# promini1via.net
KiCad netlist of a schematic drawn in EAGLE
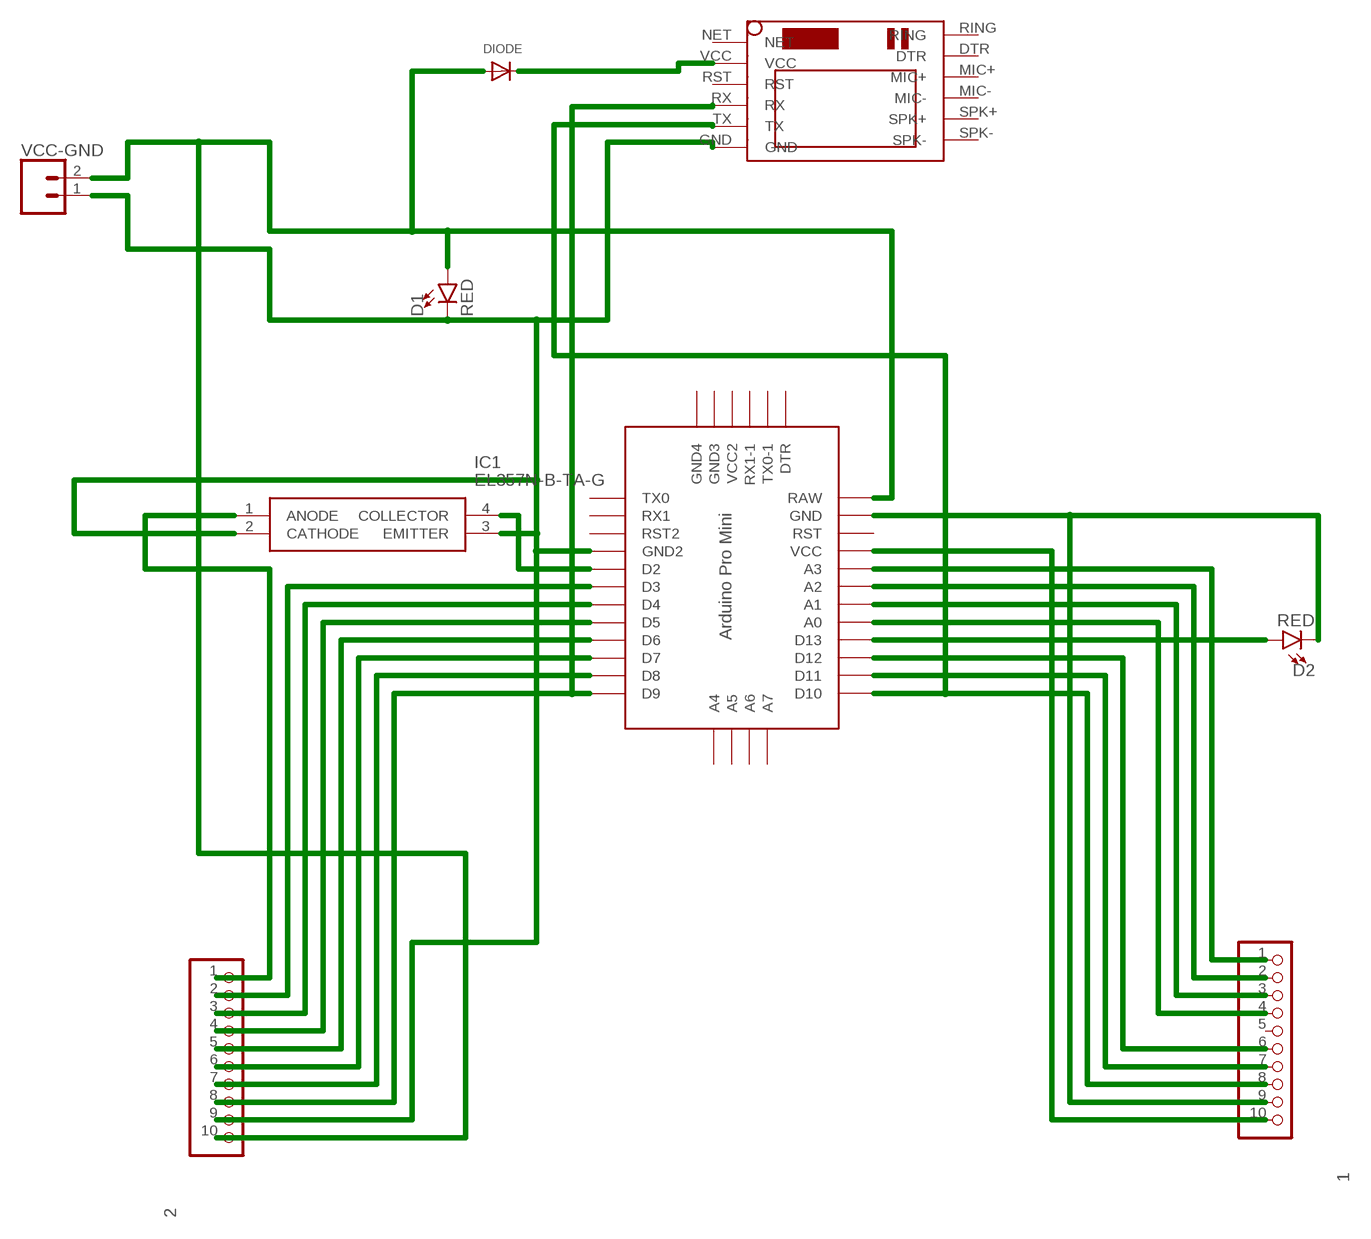
[diagram p0: schematic, sheet 1]

(export (version "E")
  (design (tool "Eeschema 10.0.6"))
  (components
    (comp (ref "1")
      (value "PINHD-1X10")
      (footprint "eagle-import:1X10")
      (libsource (lib "eagle-import") (part "PINHD-1X10"))
    )
    (comp (ref "2")
      (value "PINHD-1X10")
      (footprint "eagle-import:1X10")
      (libsource (lib "eagle-import") (part "PINHD-1X10"))
    )
    (comp (ref "D1")
      (value "RED")
      (footprint "eagle-import:LED-1206")
      (libsource (lib "eagle-import") (part "LED-RED1206"))
    )
    (comp (ref "D2")
      (value "RED")
      (footprint "eagle-import:LED-1206")
      (libsource (lib "eagle-import") (part "LED-RED1206"))
    )
    (comp (ref "DIODE")
      (value "DIODESOD-323F")
      (footprint "eagle-import:SOD-323F")
      (libsource (lib "eagle-import") (part "DIODESOD-323F"))
    )
    (comp (ref "IC1")
      (value "EL357N-B-TA-G")
      (footprint "eagle-import:SOP254P700X200-4N")
      (libsource (lib "eagle-import") (part "EL357N-B-TA-G"))
    )
    (comp (ref "PROMINI")
      (value "PRO-MINI")
      (footprint "eagle-import:PRO-MINI")
      (libsource (lib "eagle-import") (part "PRO-MINI"))
    )
    (comp (ref "U$1")
      (value "SIM800LMODULE")
      (footprint "eagle-import:SIM800LMODULE")
      (libsource (lib "eagle-import") (part "SIM800LMODULE"))
    )
    (comp (ref "VCC-GND")
      (value "CONN_023.5MM")
      (footprint "eagle-import:SCREWTERMINAL-3.5MM-2")
      (libsource (lib "eagle-import") (part "CONN_023.5MM"))
    )
  )
  (nets
    (net (code "1") (name "Net-(1-Pad1)") (class "Default")
      (node (ref "1") (pin "1") (pinfunction "1_1") (pintype "passive"))
      (node (ref "PROMINI") (pin "A3") (pinfunction "A3_A3") (pintype "bidirectional"))
    )
    (net (code "2") (name "Net-(1-Pad2)") (class "Default")
      (node (ref "1") (pin "2") (pinfunction "2_2") (pintype "passive"))
      (node (ref "PROMINI") (pin "A2") (pinfunction "A2_A2") (pintype "bidirectional"))
    )
    (net (code "3") (name "Net-(1-Pad3)") (class "Default")
      (node (ref "1") (pin "3") (pinfunction "3_3") (pintype "passive"))
      (node (ref "PROMINI") (pin "A1") (pinfunction "A1_A1") (pintype "bidirectional"))
    )
    (net (code "4") (name "Net-(1-Pad4)") (class "Default")
      (node (ref "1") (pin "4") (pinfunction "4_4") (pintype "passive"))
      (node (ref "PROMINI") (pin "A0") (pinfunction "A0_A0") (pintype "bidirectional"))
    )
    (net (code "5") (name "Net-(1-Pad6)") (class "Default")
      (node (ref "1") (pin "6") (pinfunction "6_6") (pintype "passive"))
      (node (ref "PROMINI") (pin "D12") (pinfunction "D12_D12") (pintype "bidirectional"))
    )
    (net (code "6") (name "Net-(1-Pad7)") (class "Default")
      (node (ref "1") (pin "7") (pinfunction "7_7") (pintype "passive"))
      (node (ref "PROMINI") (pin "D11") (pinfunction "D11_D11") (pintype "bidirectional"))
    )
    (net (code "7") (name "Net-(1-Pad8)") (class "Default")
      (node (ref "1") (pin "8") (pinfunction "8_8") (pintype "passive"))
      (node (ref "PROMINI") (pin "D10") (pinfunction "D10_D10") (pintype "bidirectional"))
      (node (ref "U$1") (pin "TX") (pinfunction "TX_TX") (pintype "bidirectional"))
    )
    (net (code "8") (name "Net-(1-Pad9)") (class "Default")
      (node (ref "1") (pin "9") (pinfunction "9_9") (pintype "passive"))
      (node (ref "D2") (pin "C") (pinfunction "C_C") (pintype "passive"))
      (node (ref "PROMINI") (pin "GND") (pinfunction "GND_GND") (pintype "input"))
    )
    (net (code "9") (name "Net-(1-Pad10)") (class "Default")
      (node (ref "1") (pin "10") (pinfunction "10_10") (pintype "passive"))
      (node (ref "PROMINI") (pin "VCC") (pinfunction "VCC_VCC") (pintype "bidirectional"))
    )
    (net (code "10") (name "Net-(2-Pad2)") (class "Default")
      (node (ref "2") (pin "2") (pinfunction "2_2") (pintype "passive"))
      (node (ref "PROMINI") (pin "D3") (pinfunction "D3_D3") (pintype "bidirectional"))
    )
    (net (code "11") (name "Net-(2-Pad3)") (class "Default")
      (node (ref "2") (pin "3") (pinfunction "3_3") (pintype "passive"))
      (node (ref "PROMINI") (pin "D4") (pinfunction "D4_D4") (pintype "bidirectional"))
    )
    (net (code "12") (name "Net-(2-Pad4)") (class "Default")
      (node (ref "2") (pin "4") (pinfunction "4_4") (pintype "passive"))
      (node (ref "PROMINI") (pin "D5") (pinfunction "D5_D5") (pintype "bidirectional"))
    )
    (net (code "13") (name "Net-(2-Pad5)") (class "Default")
      (node (ref "2") (pin "5") (pinfunction "5_5") (pintype "passive"))
      (node (ref "PROMINI") (pin "D6") (pinfunction "D6_D6") (pintype "bidirectional"))
    )
    (net (code "14") (name "Net-(2-Pad6)") (class "Default")
      (node (ref "2") (pin "6") (pinfunction "6_6") (pintype "passive"))
      (node (ref "PROMINI") (pin "D7") (pinfunction "D7_D7") (pintype "bidirectional"))
    )
    (net (code "15") (name "Net-(2-Pad7)") (class "Default")
      (node (ref "2") (pin "7") (pinfunction "7_7") (pintype "passive"))
      (node (ref "PROMINI") (pin "D8") (pinfunction "D8_D8") (pintype "bidirectional"))
    )
    (net (code "16") (name "Net-(2-Pad8)") (class "Default")
      (node (ref "2") (pin "8") (pinfunction "8_8") (pintype "passive"))
      (node (ref "PROMINI") (pin "D9") (pinfunction "D9_D9") (pintype "bidirectional"))
      (node (ref "U$1") (pin "RX") (pinfunction "RX_RX") (pintype "bidirectional"))
    )
    (net (code "17") (name "Net-(2-Pad10)") (class "Default")
      (node (ref "2") (pin "10") (pinfunction "10_10") (pintype "passive"))
      (node (ref "D1") (pin "A") (pinfunction "A_A") (pintype "passive"))
      (node (ref "DIODE") (pin "A") (pinfunction "A_A") (pintype "passive"))
      (node (ref "PROMINI") (pin "RAW") (pinfunction "RAW_RAW") (pintype "power_in"))
      (node (ref "VCC-GND") (pin "2") (pinfunction "2_2") (pintype "passive"))
    )
    (net (code "18") (name "Net-(D2-PadA)") (class "Default")
      (node (ref "D2") (pin "A") (pinfunction "A_A") (pintype "passive"))
      (node (ref "PROMINI") (pin "D13") (pinfunction "D13_D13") (pintype "bidirectional"))
    )
    (net (code "19") (name "Net-(DIODE-PadC)") (class "Default")
      (node (ref "DIODE") (pin "C") (pinfunction "C_C") (pintype "passive"))
      (node (ref "U$1") (pin "VCC") (pinfunction "VCC_VCC") (pintype "bidirectional"))
    )
    (net (code "20") (name "Net-(IC1-ANODE)") (class "Default")
      (node (ref "2") (pin "1") (pinfunction "1_1") (pintype "passive"))
      (node (ref "IC1") (pin "1") (pinfunction "ANODE_1") (pintype "bidirectional"))
    )
    (net (code "21") (name "Net-(IC1-CATHODE)") (class "Default")
      (node (ref "2") (pin "9") (pinfunction "9_9") (pintype "passive"))
      (node (ref "D1") (pin "C") (pinfunction "C_C") (pintype "passive"))
      (node (ref "IC1") (pin "2") (pinfunction "CATHODE_2") (pintype "bidirectional"))
      (node (ref "IC1") (pin "3") (pinfunction "EMITTER_3") (pintype "bidirectional"))
      (node (ref "PROMINI") (pin "GND1") (pinfunction "GND2_GND1") (pintype "bidirectional"))
      (node (ref "U$1") (pin "GND") (pinfunction "GND_GND") (pintype "bidirectional"))
      (node (ref "VCC-GND") (pin "1") (pinfunction "1_1") (pintype "passive"))
    )
    (net (code "22") (name "Net-(IC1-COLLECTOR)") (class "Default")
      (node (ref "IC1") (pin "4") (pinfunction "COLLECTOR_4") (pintype "bidirectional"))
      (node (ref "PROMINI") (pin "D2") (pinfunction "D2_D2") (pintype "bidirectional"))
    )
    (net (code "23") (name "unconnected-(1-Pad5)") (class "Default")
      (node (ref "1") (pin "5") (pinfunction "5_5") (pintype "passive"))
    )
    (net (code "24") (name "unconnected-(PROMINI-GND4-PadGND2)") (class "Default")
      (node (ref "PROMINI") (pin "GND2") (pinfunction "GND4_GND2") (pintype "bidirectional"))
    )
    (net (code "25") (name "unconnected-(PROMINI-PadA4)") (class "Default")
      (node (ref "PROMINI") (pin "A4") (pinfunction "A4_A4") (pintype "bidirectional"))
    )
    (net (code "26") (name "unconnected-(PROMINI-PadA5)") (class "Default")
      (node (ref "PROMINI") (pin "A5") (pinfunction "A5_A5") (pintype "bidirectional"))
    )
    (net (code "27") (name "unconnected-(PROMINI-PadA6)") (class "Default")
      (node (ref "PROMINI") (pin "A6") (pinfunction "A6_A6") (pintype "bidirectional"))
    )
    (net (code "28") (name "unconnected-(PROMINI-PadA7)") (class "Default")
      (node (ref "PROMINI") (pin "A7") (pinfunction "A7_A7") (pintype "bidirectional"))
    )
    (net (code "29") (name "unconnected-(PROMINI-PadDTR)") (class "Default")
      (node (ref "PROMINI") (pin "DTR") (pinfunction "DTR_DTR") (pintype "bidirectional"))
    )
    (net (code "30") (name "unconnected-(PROMINI-PadGND3)") (class "Default")
      (node (ref "PROMINI") (pin "GND3") (pinfunction "GND3_GND3") (pintype "bidirectional"))
    )
    (net (code "31") (name "unconnected-(PROMINI-PadRST)") (class "Default")
      (node (ref "PROMINI") (pin "RST") (pinfunction "RST_RST") (pintype "bidirectional"))
    )
    (net (code "32") (name "unconnected-(PROMINI-PadRX1)") (class "Default")
      (node (ref "PROMINI") (pin "RX1") (pinfunction "RX1_RX1") (pintype "bidirectional"))
    )
    (net (code "33") (name "unconnected-(PROMINI-PadRX1-1)") (class "Default")
      (node (ref "PROMINI") (pin "RX1-1") (pinfunction "RX1-1_RX1-1") (pintype "bidirectional"))
    )
    (net (code "34") (name "unconnected-(PROMINI-PadTX0)") (class "Default")
      (node (ref "PROMINI") (pin "TX0") (pinfunction "TX0_TX0") (pintype "bidirectional"))
    )
    (net (code "35") (name "unconnected-(PROMINI-PadTX0-1)") (class "Default")
      (node (ref "PROMINI") (pin "TX0-1") (pinfunction "TX0-1_TX0-1") (pintype "bidirectional"))
    )
    (net (code "36") (name "unconnected-(PROMINI-RST2-PadRST1)") (class "Default")
      (node (ref "PROMINI") (pin "RST1") (pinfunction "RST2_RST1") (pintype "bidirectional"))
    )
    (net (code "37") (name "unconnected-(PROMINI-VCC2-PadVCC1)") (class "Default")
      (node (ref "PROMINI") (pin "VCC1") (pinfunction "VCC2_VCC1") (pintype "bidirectional"))
    )
    (net (code "38") (name "unconnected-(U$1-PadDTR)") (class "Default")
      (node (ref "U$1") (pin "DTR") (pinfunction "DTR_DTR") (pintype "bidirectional"))
    )
    (net (code "39") (name "unconnected-(U$1-PadMIC+)") (class "Default")
      (node (ref "U$1") (pin "MIC+") (pinfunction "MIC+_MIC+") (pintype "bidirectional"))
    )
    (net (code "40") (name "unconnected-(U$1-PadMIC-)") (class "Default")
      (node (ref "U$1") (pin "MIC-") (pinfunction "MIC-_MIC-") (pintype "bidirectional"))
    )
    (net (code "41") (name "unconnected-(U$1-PadNET)") (class "Default")
      (node (ref "U$1") (pin "NET") (pinfunction "NET_NET") (pintype "bidirectional"))
    )
    (net (code "42") (name "unconnected-(U$1-PadRING)") (class "Default")
      (node (ref "U$1") (pin "RING") (pinfunction "RING_RING") (pintype "bidirectional"))
    )
    (net (code "43") (name "unconnected-(U$1-PadRST)") (class "Default")
      (node (ref "U$1") (pin "RST") (pinfunction "RST_RST") (pintype "bidirectional"))
    )
    (net (code "44") (name "unconnected-(U$1-PadSPK+)") (class "Default")
      (node (ref "U$1") (pin "SPK+") (pinfunction "SPK+_SPK+") (pintype "bidirectional"))
    )
    (net (code "45") (name "unconnected-(U$1-PadSPK-)") (class "Default")
      (node (ref "U$1") (pin "SPK-") (pinfunction "SPK-_SPK-") (pintype "bidirectional"))
    )
  )
)
